# voltage_regualtor.net
KiCad netlist of a schematic drawn in EAGLE
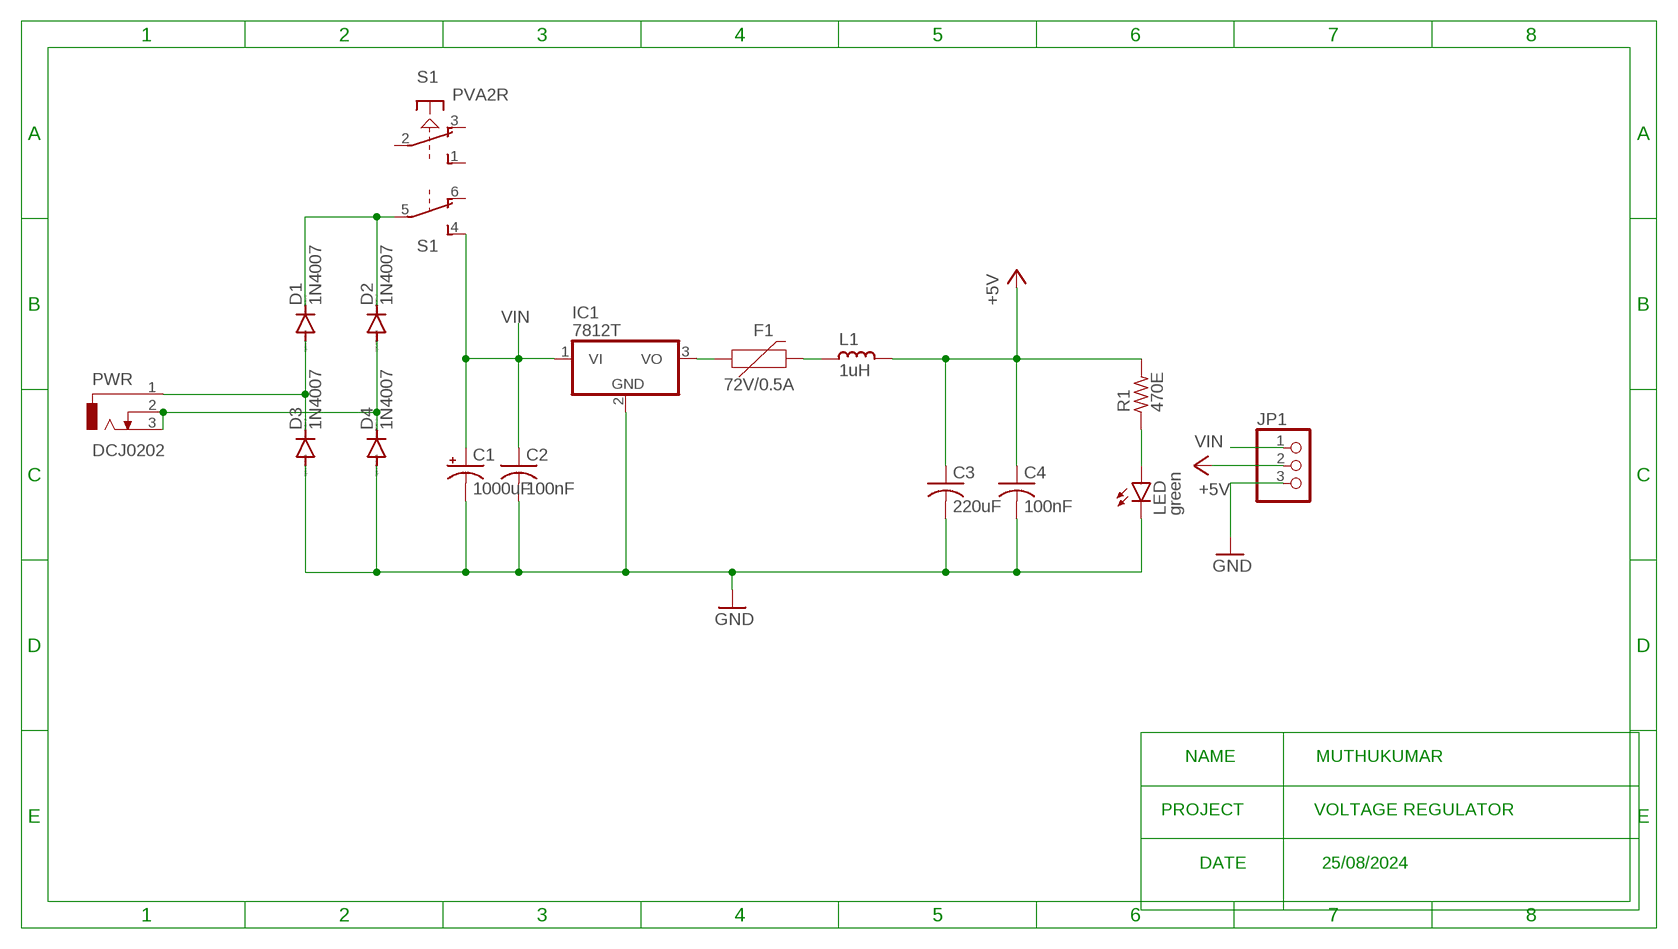
[diagram p0: schematic, sheet 1]

(export (version "E")
  (design (tool "Eeschema 10.0.6"))
  (components
    (comp (ref "C1")
      (value "1000uF")
      (footprint "eagle-import:E5-13")
      (libsource (lib "eagle-import") (part "CPOL-USE5-13"))
    )
    (comp (ref "C2")
      (value "100nF")
      (footprint "eagle-import:C0805")
      (libsource (lib "eagle-import") (part "C-USC0805"))
    )
    (comp (ref "C3")
      (value "220uF")
      (footprint "eagle-import:C0805")
      (libsource (lib "eagle-import") (part "C-USC0805"))
    )
    (comp (ref "C4")
      (value "100nF")
      (footprint "eagle-import:C0805")
      (libsource (lib "eagle-import") (part "C-USC0805"))
    )
    (comp (ref "D1")
      (value "1N4007")
      (footprint "eagle-import:DO41-10")
      (libsource (lib "eagle-import") (part "1N4004"))
    )
    (comp (ref "D2")
      (value "1N4007")
      (footprint "eagle-import:DO41-10")
      (libsource (lib "eagle-import") (part "1N4004"))
    )
    (comp (ref "D3")
      (value "1N4007")
      (footprint "eagle-import:DO41-10")
      (libsource (lib "eagle-import") (part "1N4004"))
    )
    (comp (ref "D4")
      (value "1N4007")
      (footprint "eagle-import:DO41-10")
      (libsource (lib "eagle-import") (part "1N4004"))
    )
    (comp (ref "F1")
      (value "72V/0.5A")
      (footprint "eagle-import:PTH")
      (libsource (lib "eagle-import") (part "PPTC_PTH"))
    )
    (comp (ref "IC1")
      (value "7812T")
      (footprint "eagle-import:TO220H")
      (libsource (lib "eagle-import") (part "78T12"))
    )
    (comp (ref "JP1")
      (value "PINHD-1X3")
      (footprint "eagle-import:1X03")
      (libsource (lib "eagle-import") (part "PINHD-1X3"))
    )
    (comp (ref "L1")
      (value "1uH")
      (footprint "eagle-import:L0805")
      (libsource (lib "eagle-import") (part "L_0805"))
    )
    (comp (ref "LED")
      (value "green")
      (footprint "eagle-import:CHIPLED_0805")
      (libsource (lib "eagle-import") (part "LEDCHIPLED_0805"))
    )
    (comp (ref "PWR")
      (value "DCJ0202")
      (footprint "eagle-import:DCJ0202")
      (libsource (lib "eagle-import") (part "DCJ0202"))
    )
    (comp (ref "R1")
      (value "470E")
      (footprint "eagle-import:R0805")
      (libsource (lib "eagle-import") (part "R_0805"))
    )
    (comp (ref "S1")
      (value "PVA2R")
      (footprint "eagle-import:PVA2R")
      (libsource (lib "eagle-import") (part "PVA2R"))
    )
  )
  (nets
    (net (code "1") (name "+5V") (class "Default")
      (node (ref "C3") (pin "1") (pinfunction "1_1") (pintype "passive"))
      (node (ref "C4") (pin "1") (pinfunction "1_1") (pintype "passive"))
      (node (ref "JP1") (pin "2") (pinfunction "2_2") (pintype "passive"))
      (node (ref "L1") (pin "1") (pinfunction "1_1") (pintype "passive"))
      (node (ref "R1") (pin "2") (pinfunction "2_2") (pintype "passive"))
    )
    (net (code "2") (name "/VIN") (class "Default")
      (node (ref "C1") (pin "+") (pinfunction "+_+") (pintype "passive"))
      (node (ref "C2") (pin "1") (pinfunction "1_1") (pintype "passive"))
      (node (ref "IC1") (pin "1") (pinfunction "VI_1") (pintype "input"))
      (node (ref "JP1") (pin "1") (pinfunction "1_1") (pintype "passive"))
      (node (ref "S1") (pin "4") (pinfunction "S_4") (pintype "passive"))
    )
    (net (code "3") (name "GND") (class "Default")
      (node (ref "C1") (pin "-") (pinfunction "-_-") (pintype "passive"))
      (node (ref "C2") (pin "2") (pinfunction "2_2") (pintype "passive"))
      (node (ref "C3") (pin "2") (pinfunction "2_2") (pintype "passive"))
      (node (ref "C4") (pin "2") (pinfunction "2_2") (pintype "passive"))
      (node (ref "D3") (pin "A") (pinfunction "A_A") (pintype "passive"))
      (node (ref "D4") (pin "A") (pinfunction "A_A") (pintype "passive"))
      (node (ref "IC1") (pin "2") (pinfunction "GND_2") (pintype "passive"))
      (node (ref "JP1") (pin "3") (pinfunction "3_3") (pintype "passive"))
      (node (ref "LED") (pin "C") (pinfunction "C_C") (pintype "passive"))
    )
    (net (code "4") (name "Net-(D1-PadA)") (class "Default")
      (node (ref "D1") (pin "A") (pinfunction "A_A") (pintype "passive"))
      (node (ref "D3") (pin "C") (pinfunction "C_C") (pintype "passive"))
      (node (ref "PWR") (pin "1") (pinfunction "1_1") (pintype "passive"))
    )
    (net (code "5") (name "Net-(D2-PadA)") (class "Default")
      (node (ref "D2") (pin "A") (pinfunction "A_A") (pintype "passive"))
      (node (ref "D4") (pin "C") (pinfunction "C_C") (pintype "passive"))
      (node (ref "PWR") (pin "2") (pinfunction "2_2") (pintype "passive"))
      (node (ref "PWR") (pin "3") (pinfunction "3_3") (pintype "passive"))
    )
    (net (code "6") (name "Net-(F1-1)") (class "Default")
      (node (ref "F1") (pin "P$1") (pinfunction "1_P$1") (pintype "bidirectional"))
      (node (ref "IC1") (pin "3") (pinfunction "VO_3") (pintype "passive"))
    )
    (net (code "7") (name "Net-(F1-2)") (class "Default")
      (node (ref "F1") (pin "P$2") (pinfunction "2_P$2") (pintype "bidirectional"))
      (node (ref "L1") (pin "2") (pinfunction "2_2") (pintype "passive"))
    )
    (net (code "8") (name "Net-(LED-PadA)") (class "Default")
      (node (ref "LED") (pin "A") (pinfunction "A_A") (pintype "passive"))
      (node (ref "R1") (pin "1") (pinfunction "1_1") (pintype "passive"))
    )
    (net (code "9") (name "Net-(S1B-P)") (class "Default")
      (node (ref "D1") (pin "C") (pinfunction "C_C") (pintype "passive"))
      (node (ref "D2") (pin "C") (pinfunction "C_C") (pintype "passive"))
      (node (ref "S1") (pin "5") (pinfunction "P_5") (pintype "passive"))
    )
    (net (code "10") (name "unconnected-(S1A-O-Pad3)") (class "Default")
      (node (ref "S1") (pin "3") (pinfunction "O_3") (pintype "passive"))
    )
    (net (code "11") (name "unconnected-(S1A-P-Pad2)") (class "Default")
      (node (ref "S1") (pin "2") (pinfunction "P_2") (pintype "passive"))
    )
    (net (code "12") (name "unconnected-(S1A-S-Pad1)") (class "Default")
      (node (ref "S1") (pin "1") (pinfunction "S_1") (pintype "passive"))
    )
    (net (code "13") (name "unconnected-(S1B-O-Pad6)") (class "Default")
      (node (ref "S1") (pin "6") (pinfunction "O_6") (pintype "passive"))
    )
  )
)
